# middlePCB_rev3.net
KiCad netlist of a schematic drawn in Altium Designer
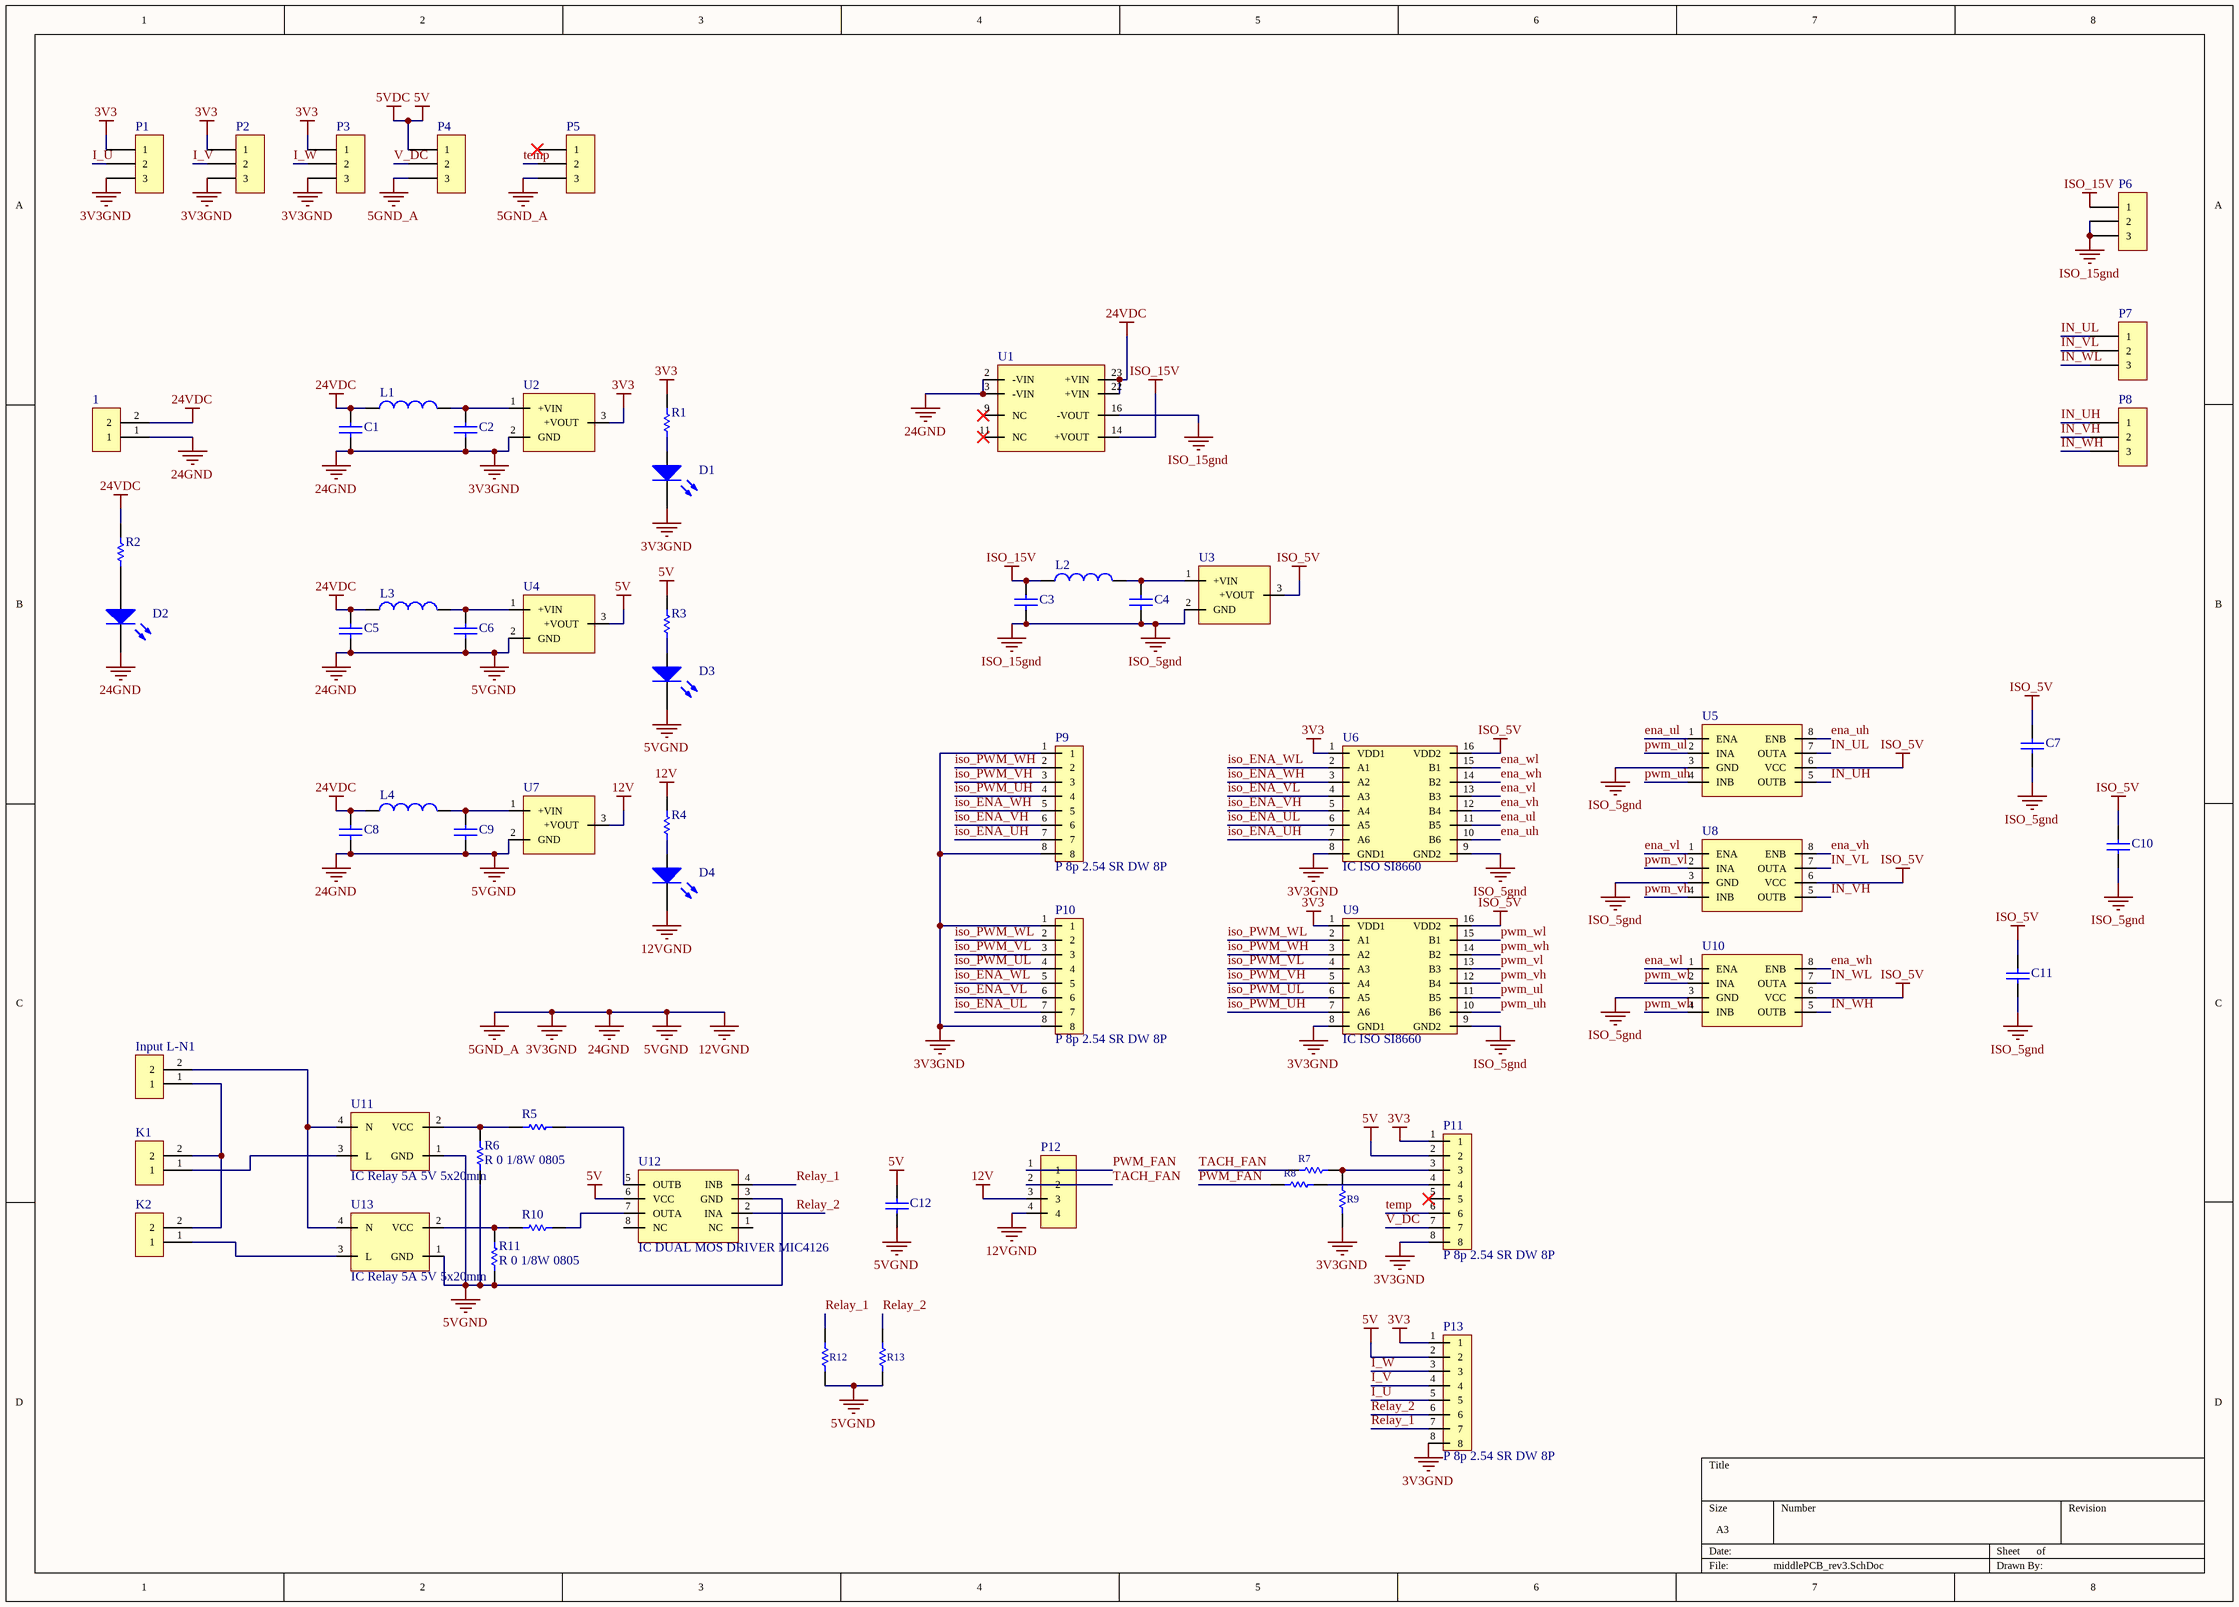
[diagram p0: middlePCB_rev3.SchDoc]

(export (version "E")
  (design (tool "Eeschema 10.0.6"))
  (components
    (comp (ref "1")
      (value "P 2p 5mm")
      (footprint "connector1x2_parafuso")
      (description "Bloques de terminales de PCB de perfil estándar RS de 5,0 mm")
      (libsource (lib "vmorais_libraries") (part "gen_purpose_conn_1x2"))
    )
    (comp (ref "C1")
      (value "C 10uF 1206 MLCC 50V X5R")
      (footprint "CAPC_1206")
      (description "Capacitores de cerâmica multicamada MLCC - SMD/SMT 1206 50V 10uF 20% X5R")
      (libsource (lib "vmorais_libraries") (part "Capacitor SMD"))
    )
    (comp (ref "C2")
      (value "C 10uF 1206 MLCC 50V X5R")
      (footprint "CAPC_1206")
      (description "Capacitores de cerâmica multicamada MLCC - SMD/SMT 1206 50V 10uF 20% X5R")
      (libsource (lib "vmorais_libraries") (part "Capacitor SMD"))
    )
    (comp (ref "C3")
      (value "C 10uF 1206 MLCC 50V X5R")
      (footprint "CAPC_1206")
      (description "Capacitores de cerâmica multicamada MLCC - SMD/SMT 1206 50V 10uF 20% X5R")
      (libsource (lib "vmorais_libraries") (part "Capacitor SMD"))
    )
    (comp (ref "C4")
      (value "C 10uF 1206 MLCC 50V X5R")
      (footprint "CAPC_1206")
      (description "Capacitores de cerâmica multicamada MLCC - SMD/SMT 1206 50V 10uF 20% X5R")
      (libsource (lib "vmorais_libraries") (part "Capacitor SMD"))
    )
    (comp (ref "C5")
      (value "C 10uF 1206 MLCC 50V X5R")
      (footprint "CAPC_1206")
      (description "Capacitores de cerâmica multicamada MLCC - SMD/SMT 1206 50V 10uF 20% X5R")
      (libsource (lib "vmorais_libraries") (part "Capacitor SMD"))
    )
    (comp (ref "C6")
      (value "C 10uF 1206 MLCC 50V X5R")
      (footprint "CAPC_1206")
      (description "Capacitores de cerâmica multicamada MLCC - SMD/SMT 1206 50V 10uF 20% X5R")
      (libsource (lib "vmorais_libraries") (part "Capacitor SMD"))
    )
    (comp (ref "C7")
      (value "C 10uF 1206 MLCC 50V X5R")
      (footprint "CAPC_1206")
      (description "Capacitores de cerâmica multicamada MLCC - SMD/SMT 1206 50V 10uF 20% X5R")
      (libsource (lib "vmorais_libraries") (part "Capacitor SMD"))
    )
    (comp (ref "C8")
      (value "C 10uF 1206 MLCC 50V X5R")
      (footprint "CAPC_1206")
      (description "Capacitores de cerâmica multicamada MLCC - SMD/SMT 1206 50V 10uF 20% X5R")
      (libsource (lib "vmorais_libraries") (part "Capacitor SMD"))
    )
    (comp (ref "C9")
      (value "C 10uF 1206 MLCC 50V X5R")
      (footprint "CAPC_1206")
      (description "Capacitores de cerâmica multicamada MLCC - SMD/SMT 1206 50V 10uF 20% X5R")
      (libsource (lib "vmorais_libraries") (part "Capacitor SMD"))
    )
    (comp (ref "C10")
      (value "C 10uF 1206 MLCC 50V X5R")
      (footprint "CAPC_1206")
      (description "Capacitores de cerâmica multicamada MLCC - SMD/SMT 1206 50V 10uF 20% X5R")
      (libsource (lib "vmorais_libraries") (part "Capacitor SMD"))
    )
    (comp (ref "C11")
      (value "C 10uF 1206 MLCC 50V X5R")
      (footprint "CAPC_1206")
      (description "Capacitores de cerâmica multicamada MLCC - SMD/SMT 1206 50V 10uF 20% X5R")
      (libsource (lib "vmorais_libraries") (part "Capacitor SMD"))
    )
    (comp (ref "C12")
      (value "C 10uF 1206 MLCC 50V X5R")
      (footprint "CAPC_1206")
      (description "Capacitores de cerâmica multicamada MLCC - SMD/SMT 1206 50V 10uF 20% X5R")
      (libsource (lib "vmorais_libraries") (part "Capacitor SMD"))
    )
    (comp (ref "D1")
      (value "IC LED 1206")
      (footprint "DIODE_1206")
      (description "LEDs padrão - SMD GREEN WATER CLEAR")
      (libsource (lib "vmorais_libraries") (part "LED"))
    )
    (comp (ref "D2")
      (value "IC LED 1206")
      (footprint "DIODE_1206")
      (description "LEDs padrão - SMD GREEN WATER CLEAR")
      (libsource (lib "vmorais_libraries") (part "LED"))
    )
    (comp (ref "D3")
      (value "IC LED 1206")
      (footprint "DIODE_1206")
      (description "LEDs padrão - SMD GREEN WATER CLEAR")
      (libsource (lib "vmorais_libraries") (part "LED"))
    )
    (comp (ref "D4")
      (value "IC LED 1206")
      (footprint "DIODE_1206")
      (description "LEDs padrão - SMD GREEN WATER CLEAR")
      (libsource (lib "vmorais_libraries") (part "LED"))
    )
    (comp (ref "Input L-N1")
      (value "P 2p 5mm")
      (footprint "connector1x2_parafuso")
      (description "Bloques de terminales de PCB de perfil estándar RS de 5,0 mm")
      (libsource (lib "vmorais_libraries") (part "gen_purpose_conn_1x2"))
    )
    (comp (ref "K1")
      (value "P 2p 5mm")
      (footprint "connector1x2_parafuso")
      (description "Bloques de terminales de PCB de perfil estándar RS de 5,0 mm")
      (libsource (lib "vmorais_libraries") (part "gen_purpose_conn_1x2"))
    )
    (comp (ref "K2")
      (value "P 2p 5mm")
      (footprint "connector1x2_parafuso")
      (description "Bloques de terminales de PCB de perfil estándar RS de 5,0 mm")
      (libsource (lib "vmorais_libraries") (part "gen_purpose_conn_1x2"))
    )
    (comp (ref "L1")
      (value "IND RLS-126")
      (footprint "Inductor - RLS-126")
      (description "Indutores fixos Line Inductors for RECOM Power Supply")
      (libsource (lib "vmorais_libraries") (part "Inductor"))
    )
    (comp (ref "L2")
      (value "IND RLS-126")
      (footprint "Inductor - RLS-126")
      (description "Indutores fixos Line Inductors for RECOM Power Supply")
      (libsource (lib "vmorais_libraries") (part "Inductor"))
    )
    (comp (ref "L3")
      (value "IND RLS-126")
      (footprint "Inductor - RLS-126")
      (description "Indutores fixos Line Inductors for RECOM Power Supply")
      (libsource (lib "vmorais_libraries") (part "Inductor"))
    )
    (comp (ref "L4")
      (value "IND RLS-126")
      (footprint "Inductor - RLS-126")
      (description "Indutores fixos Line Inductors for RECOM Power Supply")
      (libsource (lib "vmorais_libraries") (part "Inductor"))
    )
    (comp (ref "P1")
      (value "P 8p 2.54 SR DW 3P")
      (footprint "MOLEX_3p_105431_1103")
      (description "Distribuidores e Alojamento de Fios CGrid Hrd SRDW THo le 8ckt")
      (libsource (lib "vmorais_libraries") (part "Header 3"))
    )
    (comp (ref "P2")
      (value "P 8p 2.54 SR DW 3P")
      (footprint "MOLEX_3p_105431_1103")
      (description "Distribuidores e Alojamento de Fios CGrid Hrd SRDW THo le 8ckt")
      (libsource (lib "vmorais_libraries") (part "Header 3"))
    )
    (comp (ref "P3")
      (value "P 8p 2.54 SR DW 3P")
      (footprint "MOLEX_3p_105431_1103")
      (description "Distribuidores e Alojamento de Fios CGrid Hrd SRDW THo le 8ckt")
      (libsource (lib "vmorais_libraries") (part "Header 3"))
    )
    (comp (ref "P4")
      (value "P 8p 2.54 SR DW 3P")
      (footprint "MOLEX_3p_105431_1103")
      (description "Distribuidores e Alojamento de Fios CGrid Hrd SRDW THo le 8ckt")
      (libsource (lib "vmorais_libraries") (part "Header 3"))
    )
    (comp (ref "P5")
      (value "P 8p 2.54 SR DW 3P")
      (footprint "MOLEX_3p_105431_1103")
      (description "Distribuidores e Alojamento de Fios CGrid Hrd SRDW THo le 8ckt")
      (libsource (lib "vmorais_libraries") (part "Header 3"))
    )
    (comp (ref "P6")
      (value "P 8p 2.54 SR DW 3P")
      (footprint "MOLEX_3p_105431_1103")
      (description "Distribuidores e Alojamento de Fios CGrid Hrd SRDW THo le 8ckt")
      (libsource (lib "vmorais_libraries") (part "Header 3"))
    )
    (comp (ref "P7")
      (value "P 8p 2.54 SR DW 3P")
      (footprint "MOLEX_3p_105431_1103")
      (description "Distribuidores e Alojamento de Fios CGrid Hrd SRDW THo le 8ckt")
      (libsource (lib "vmorais_libraries") (part "Header 3"))
    )
    (comp (ref "P8")
      (value "P 8p 2.54 SR DW 3P")
      (footprint "MOLEX_3p_105431_1103")
      (description "Distribuidores e Alojamento de Fios CGrid Hrd SRDW THo le 8ckt")
      (libsource (lib "vmorais_libraries") (part "Header 3"))
    )
    (comp (ref "P9")
      (value "P 8p 2.54 SR DW 8P")
      (footprint "Header 8x1 8.5mm")
      (description "Distribuidores e Alojamento de Fios CGrid Hrd SRDW THo le 8ckt")
      (libsource (lib "vmorais_libraries") (part "jumper_8p"))
    )
    (comp (ref "P10")
      (value "P 8p 2.54 SR DW 8P")
      (footprint "Header 8x1 8.5mm")
      (description "Distribuidores e Alojamento de Fios CGrid Hrd SRDW THo le 8ckt")
      (libsource (lib "vmorais_libraries") (part "jumper_8p"))
    )
    (comp (ref "P11")
      (value "P 8p 2.54 SR DW 8P")
      (footprint "Header 8x1 8.5mm")
      (description "Distribuidores e Alojamento de Fios CGrid Hrd SRDW THo le 8ckt")
      (libsource (lib "vmorais_libraries") (part "jumper_8p"))
    )
    (comp (ref "P12")
      (value "P 4p 2.54 MOL FAN")
      (footprint "HEADER 4p molex")
      (description "Distribuidores e Alojamento de Fios 4 PIN HEADER WITH FR R WITH FRICTION LOCK")
      (libsource (lib "vmorais_libraries") (part "Header 4p molex"))
    )
    (comp (ref "P13")
      (value "P 8p 2.54 SR DW 8P")
      (footprint "Header 8x1 8.5mm")
      (description "Distribuidores e Alojamento de Fios CGrid Hrd SRDW THo le 8ckt")
      (libsource (lib "vmorais_libraries") (part "jumper_8p"))
    )
    (comp (ref "R1")
      (value "R 150 1/8W 0805 1%")
      (footprint "RESC_0805")
      (description "Resistores de Filme Espesso - SMD 1/8watt 150ohms 1% 100ppm")
      (libsource (lib "vmorais_libraries") (part "Resistor"))
    )
    (comp (ref "R2")
      (value "R 2k7 1/8 0805 1%")
      (footprint "RESC_0805")
      (description "Resistores de Filme Espesso - SMD 1/8watt 2.7Kohms 1% 100ppm")
      (libsource (lib "vmorais_libraries") (part "Resistor"))
    )
    (comp (ref "R3")
      (value "R 330 1/8 0805 1%")
      (footprint "RESC_0805")
      (description "Resistores de Filme Espesso - SMD 1/8Watt 330ohms 1% Commercial Use")
      (libsource (lib "vmorais_libraries") (part "Resistor"))
    )
    (comp (ref "R4")
      (value "R 1k2 1/8 0805 1%")
      (footprint "RESC_0805")
      (description "Resistores de Filme Espesso - SMD 1/8watt 1.2Kohms 1%")
      (libsource (lib "vmorais_libraries") (part "Resistor"))
    )
    (comp (ref "R5")
      (value "R 10 1/8W 0805 1%")
      (footprint "RESC_0805")
      (description "Resistores de Filme Espesso - SMD 1/8Watt 10ohms 1% Commercial Use")
      (libsource (lib "vmorais_libraries") (part "Resistor"))
    )
    (comp (ref "R6")
      (value "R 0 1/8W 0805")
      (footprint "RESC_0805")
      (description "Resistores de Filme Espesso - SMD 1/8Watt 0ohms Commercial Use")
      (libsource (lib "vmorais_libraries") (part "Resistor"))
    )
    (comp (ref "R7")
      (value "R 0 1/8W 0805")
      (footprint "RESC_0805")
      (description "Resistores de Filme Espesso - SMD 1/8Watt 0ohms Commercial Use")
      (libsource (lib "inversor_50a") (part "Resistor"))
    )
    (comp (ref "R8")
      (value "R 0 1/8W 0805")
      (footprint "RESC_0805")
      (description "Resistores de Filme Espesso - SMD 1/8Watt 0ohms Commercial Use")
      (libsource (lib "inversor_50a") (part "Resistor"))
    )
    (comp (ref "R9")
      (value "R 0 1/8W 0805")
      (footprint "RESC_0805")
      (description "Resistores de Filme Espesso - SMD 1/8Watt 0ohms Commercial Use")
      (libsource (lib "inversor_50a") (part "Resistor"))
    )
    (comp (ref "R10")
      (value "R 10 1/8W 0805 1%")
      (footprint "RESC_0805")
      (description "Resistores de Filme Espesso - SMD 1/8Watt 10ohms 1% Commercial Use")
      (libsource (lib "vmorais_libraries") (part "Resistor"))
    )
    (comp (ref "R11")
      (value "R 0 1/8W 0805")
      (footprint "RESC_0805")
      (description "Resistores de Filme Espesso - SMD 1/8Watt 0ohms Commercial Use")
      (libsource (lib "vmorais_libraries") (part "Resistor"))
    )
    (comp (ref "R12")
      (value "R 0 1/8W 0805")
      (footprint "RESC_0805")
      (description "Resistores de Filme Espesso - SMD 1/8Watt 0ohms Commercial Use")
      (libsource (lib "inversor_50a") (part "Resistor"))
    )
    (comp (ref "R13")
      (value "R 0 1/8W 0805")
      (footprint "RESC_0805")
      (description "Resistores de Filme Espesso - SMD 1/8Watt 0ohms Commercial Use")
      (libsource (lib "inversor_50a") (part "Resistor"))
    )
    (comp (ref "U1")
      (value "IC DC/DC 15V ISO")
      (footprint "MeanWell SCWNo6")
      (description "Conversores CC/CC com isolação 6W 18-36Vin 15Vout 400mA DIP24 Iso")
      (libsource (lib "vmorais_libraries") (part "MEANWELL - SCWN06"))
    )
    (comp (ref "U2")
      (value "IC DC/DC 3V3")
      (footprint "DC/DC - R-78E3.3")
      (description "Conversores CC/CC sem isolação 3.3V 500MA OUT THRU")
      (libsource (lib "vmorais_libraries") (part "DC/DC - R-78E3.3"))
    )
    (comp (ref "U3")
      (value "IC DC/DC 5V")
      (footprint "DC/DC - OKI-78SR-E")
      (description "Conversores CC/CC sem isolação 7-36Vin 5Vout 1.5A VSIP Encapsulated")
      (libsource (lib "vmorais_libraries") (part "DC/DC - R-78E3.3"))
    )
    (comp (ref "U4")
      (value "IC DC/DC 5V")
      (footprint "DC/DC - OKI-78SR-E")
      (description "Conversores CC/CC sem isolação 7-36Vin 5Vout 1.5A VSIP Encapsulated")
      (libsource (lib "vmorais_libraries") (part "DC/DC - R-78E3.3"))
    )
    (comp (ref "U5")
      (value "IC Driver 5A Dual ENA IX4340")
      (footprint "SOIC-MIC4126")
      (description "Drivers de portas Dual 5A Gate Driver IC")
      (libsource (lib "vmorais_libraries") (part "Driver - IX4340"))
    )
    (comp (ref "U6")
      (value "IC ISO SI8660")
      (footprint "SOIC127P610X155-16N")
      (description "Isoladores digitais 1 kV 6-channel digital isolator")
      (libsource (lib "vmorais_libraries") (part "ISO SI8660"))
    )
    (comp (ref "U7")
      (value "IC DC/DC 12V")
      (footprint "DC/DC - OKI-78SR-E")
      (description "Conversores CC/CC sem isolação 15-36Vin 12Vout 1.0A VSIP Encapsulated")
      (libsource (lib "vmorais_libraries") (part "DC/DC - R-78E3.3"))
    )
    (comp (ref "U8")
      (value "IC Driver 5A Dual ENA IX4340")
      (footprint "SOIC-MIC4126")
      (description "Drivers de portas Dual 5A Gate Driver IC")
      (libsource (lib "vmorais_libraries") (part "Driver - IX4340"))
    )
    (comp (ref "U9")
      (value "IC ISO SI8660")
      (footprint "SOIC127P610X155-16N")
      (description "Isoladores digitais 1 kV 6-channel digital isolator")
      (libsource (lib "vmorais_libraries") (part "ISO SI8660"))
    )
    (comp (ref "U10")
      (value "IC Driver 5A Dual ENA IX4340")
      (footprint "SOIC-MIC4126")
      (description "Drivers de portas Dual 5A Gate Driver IC")
      (libsource (lib "vmorais_libraries") (part "Driver - IX4340"))
    )
    (comp (ref "U11")
      (value "IC Relay 5A 5V 5x20mm")
      (footprint "Relay - G6DN")
      (description "Relés para uso geral 1 form A w/ 5VDC Coil-standard type")
      (libsource (lib "vmorais_libraries") (part "Relay - G6DN"))
    )
    (comp (ref "U12")
      (value "IC DUAL MOS DRIVER MIC4126")
      (footprint "SOIC-MIC4126")
      (description "Drivers de portas 1.5A Dual High Speed MOSFET Driver with Low Thermal Impedance")
      (libsource (lib "vmorais_libraries") (part "MOS_DRIVER-MIC4126"))
    )
    (comp (ref "U13")
      (value "IC Relay 5A 5V 5x20mm")
      (footprint "Relay - G6DN")
      (description "Relés para uso geral 1 form A w/ 5VDC Coil-standard type")
      (libsource (lib "vmorais_libraries") (part "Relay - G6DN"))
    )
  )
  (nets
    (net (code "1") (name "/IN_UH") (class "Default")
      (node (ref "P8") (pin "1") (pinfunction "1_1") (pintype "passive"))
      (node (ref "U5") (pin "5") (pinfunction "OUTB_5") (pintype "passive"))
    )
    (net (code "2") (name "/IN_UL") (class "Default")
      (node (ref "P7") (pin "1") (pinfunction "1_1") (pintype "passive"))
      (node (ref "U5") (pin "7") (pinfunction "OUTA_7") (pintype "passive"))
    )
    (net (code "3") (name "/IN_VH") (class "Default")
      (node (ref "P8") (pin "2") (pinfunction "2_2") (pintype "passive"))
      (node (ref "U8") (pin "5") (pinfunction "OUTB_5") (pintype "passive"))
    )
    (net (code "4") (name "/IN_VL") (class "Default")
      (node (ref "P7") (pin "2") (pinfunction "2_2") (pintype "passive"))
      (node (ref "U8") (pin "7") (pinfunction "OUTA_7") (pintype "passive"))
    )
    (net (code "5") (name "/IN_WH") (class "Default")
      (node (ref "P8") (pin "3") (pinfunction "3_3") (pintype "passive"))
      (node (ref "U10") (pin "5") (pinfunction "OUTB_5") (pintype "passive"))
    )
    (net (code "6") (name "/IN_WL") (class "Default")
      (node (ref "P7") (pin "3") (pinfunction "3_3") (pintype "passive"))
      (node (ref "U10") (pin "7") (pinfunction "OUTA_7") (pintype "passive"))
    )
    (net (code "7") (name "/I_U") (class "Default")
      (node (ref "P1") (pin "2") (pinfunction "2_2") (pintype "passive"))
      (node (ref "P13") (pin "5") (pinfunction "5_5") (pintype "passive"))
    )
    (net (code "8") (name "/I_V") (class "Default")
      (node (ref "P13") (pin "4") (pinfunction "4_4") (pintype "passive"))
      (node (ref "P2") (pin "2") (pinfunction "2_2") (pintype "passive"))
    )
    (net (code "9") (name "/I_W") (class "Default")
      (node (ref "P13") (pin "3") (pinfunction "3_3") (pintype "passive"))
      (node (ref "P3") (pin "2") (pinfunction "2_2") (pintype "passive"))
    )
    (net (code "10") (name "/PWM_FAN") (class "Default")
      (node (ref "P12") (pin "1") (pinfunction "1_1") (pintype "passive"))
      (node (ref "R8") (pin "1") (pinfunction "1_1") (pintype "passive"))
    )
    (net (code "11") (name "/Relay_1") (class "Default")
      (node (ref "P13") (pin "7") (pinfunction "7_7") (pintype "passive"))
      (node (ref "R12") (pin "2") (pinfunction "2_2") (pintype "passive"))
      (node (ref "U12") (pin "4") (pinfunction "INB_4") (pintype "passive"))
    )
    (net (code "12") (name "/Relay_2") (class "Default")
      (node (ref "P13") (pin "6") (pinfunction "6_6") (pintype "passive"))
      (node (ref "R13") (pin "2") (pinfunction "2_2") (pintype "passive"))
      (node (ref "U12") (pin "2") (pinfunction "INA_2") (pintype "passive"))
    )
    (net (code "13") (name "/TACH_FAN") (class "Default")
      (node (ref "P12") (pin "2") (pinfunction "2_2") (pintype "passive"))
      (node (ref "R7") (pin "1") (pinfunction "1_1") (pintype "passive"))
    )
    (net (code "14") (name "/V_DC") (class "Default")
      (node (ref "P11") (pin "7") (pinfunction "7_7") (pintype "passive"))
      (node (ref "P4") (pin "2") (pinfunction "2_2") (pintype "passive"))
    )
    (net (code "15") (name "/ena_uh") (class "Default")
      (node (ref "U5") (pin "8") (pinfunction "ENB_8") (pintype "passive"))
      (node (ref "U6") (pin "10") (pinfunction "B6_10") (pintype "passive"))
    )
    (net (code "16") (name "/ena_ul") (class "Default")
      (node (ref "U5") (pin "1") (pinfunction "ENA_1") (pintype "passive"))
      (node (ref "U6") (pin "11") (pinfunction "B5_11") (pintype "passive"))
    )
    (net (code "17") (name "/ena_vh") (class "Default")
      (node (ref "U6") (pin "12") (pinfunction "B4_12") (pintype "passive"))
      (node (ref "U8") (pin "8") (pinfunction "ENB_8") (pintype "passive"))
    )
    (net (code "18") (name "/ena_vl") (class "Default")
      (node (ref "U6") (pin "13") (pinfunction "B3_13") (pintype "passive"))
      (node (ref "U8") (pin "1") (pinfunction "ENA_1") (pintype "passive"))
    )
    (net (code "19") (name "/ena_wh") (class "Default")
      (node (ref "U10") (pin "8") (pinfunction "ENB_8") (pintype "passive"))
      (node (ref "U6") (pin "14") (pinfunction "B2_14") (pintype "passive"))
    )
    (net (code "20") (name "/ena_wl") (class "Default")
      (node (ref "U10") (pin "1") (pinfunction "ENA_1") (pintype "passive"))
      (node (ref "U6") (pin "15") (pinfunction "B1_15") (pintype "passive"))
    )
    (net (code "21") (name "/iso_ENA_UH") (class "Default")
      (node (ref "P9") (pin "7") (pinfunction "7_7") (pintype "passive"))
      (node (ref "U6") (pin "7") (pinfunction "A6_7") (pintype "passive"))
    )
    (net (code "22") (name "/iso_ENA_UL") (class "Default")
      (node (ref "P10") (pin "7") (pinfunction "7_7") (pintype "passive"))
      (node (ref "U6") (pin "6") (pinfunction "A5_6") (pintype "passive"))
    )
    (net (code "23") (name "/iso_ENA_VH") (class "Default")
      (node (ref "P9") (pin "6") (pinfunction "6_6") (pintype "passive"))
      (node (ref "U6") (pin "5") (pinfunction "A4_5") (pintype "passive"))
    )
    (net (code "24") (name "/iso_ENA_VL") (class "Default")
      (node (ref "P10") (pin "6") (pinfunction "6_6") (pintype "passive"))
      (node (ref "U6") (pin "4") (pinfunction "A3_4") (pintype "passive"))
    )
    (net (code "25") (name "/iso_ENA_WH") (class "Default")
      (node (ref "P9") (pin "5") (pinfunction "5_5") (pintype "passive"))
      (node (ref "U6") (pin "3") (pinfunction "A2_3") (pintype "passive"))
    )
    (net (code "26") (name "/iso_ENA_WL") (class "Default")
      (node (ref "P10") (pin "5") (pinfunction "5_5") (pintype "passive"))
      (node (ref "U6") (pin "2") (pinfunction "A1_2") (pintype "passive"))
    )
    (net (code "27") (name "/iso_PWM_UH") (class "Default")
      (node (ref "P9") (pin "4") (pinfunction "4_4") (pintype "passive"))
      (node (ref "U9") (pin "7") (pinfunction "A6_7") (pintype "passive"))
    )
    (net (code "28") (name "/iso_PWM_UL") (class "Default")
      (node (ref "P10") (pin "4") (pinfunction "4_4") (pintype "passive"))
      (node (ref "U9") (pin "6") (pinfunction "A5_6") (pintype "passive"))
    )
    (net (code "29") (name "/iso_PWM_VH") (class "Default")
      (node (ref "P9") (pin "3") (pinfunction "3_3") (pintype "passive"))
      (node (ref "U9") (pin "5") (pinfunction "A4_5") (pintype "passive"))
    )
    (net (code "30") (name "/iso_PWM_VL") (class "Default")
      (node (ref "P10") (pin "3") (pinfunction "3_3") (pintype "passive"))
      (node (ref "U9") (pin "4") (pinfunction "A3_4") (pintype "passive"))
    )
    (net (code "31") (name "/iso_PWM_WH") (class "Default")
      (node (ref "P9") (pin "2") (pinfunction "2_2") (pintype "passive"))
      (node (ref "U9") (pin "3") (pinfunction "A2_3") (pintype "passive"))
    )
    (net (code "32") (name "/iso_PWM_WL") (class "Default")
      (node (ref "P10") (pin "2") (pinfunction "2_2") (pintype "passive"))
      (node (ref "U9") (pin "2") (pinfunction "A1_2") (pintype "passive"))
    )
    (net (code "33") (name "/pwm_uh") (class "Default")
      (node (ref "U5") (pin "4") (pinfunction "INB_4") (pintype "passive"))
      (node (ref "U9") (pin "10") (pinfunction "B6_10") (pintype "passive"))
    )
    (net (code "34") (name "/pwm_ul") (class "Default")
      (node (ref "U5") (pin "2") (pinfunction "INA_2") (pintype "passive"))
      (node (ref "U9") (pin "11") (pinfunction "B5_11") (pintype "passive"))
    )
    (net (code "35") (name "/pwm_vh") (class "Default")
      (node (ref "U8") (pin "4") (pinfunction "INB_4") (pintype "passive"))
      (node (ref "U9") (pin "12") (pinfunction "B4_12") (pintype "passive"))
    )
    (net (code "36") (name "/pwm_vl") (class "Default")
      (node (ref "U8") (pin "2") (pinfunction "INA_2") (pintype "passive"))
      (node (ref "U9") (pin "13") (pinfunction "B3_13") (pintype "passive"))
    )
    (net (code "37") (name "/pwm_wh") (class "Default")
      (node (ref "U10") (pin "4") (pinfunction "INB_4") (pintype "passive"))
      (node (ref "U9") (pin "14") (pinfunction "B2_14") (pintype "passive"))
    )
    (net (code "38") (name "/pwm_wl") (class "Default")
      (node (ref "U10") (pin "2") (pinfunction "INA_2") (pintype "passive"))
      (node (ref "U9") (pin "15") (pinfunction "B1_15") (pintype "passive"))
    )
    (net (code "39") (name "/temp") (class "Default")
      (node (ref "P11") (pin "6") (pinfunction "6_6") (pintype "passive"))
      (node (ref "P5") (pin "2") (pinfunction "2_2") (pintype "passive"))
    )
    (net (code "40") (name "3V3") (class "Default")
      (node (ref "P1") (pin "1") (pinfunction "1_1") (pintype "passive"))
      (node (ref "P11") (pin "1") (pinfunction "1_1") (pintype "passive"))
      (node (ref "P13") (pin "1") (pinfunction "1_1") (pintype "passive"))
      (node (ref "P2") (pin "1") (pinfunction "1_1") (pintype "passive"))
      (node (ref "P3") (pin "1") (pinfunction "1_1") (pintype "passive"))
      (node (ref "R1") (pin "2") (pinfunction "2_2") (pintype "passive"))
      (node (ref "U2") (pin "3") (pinfunction "+VOUT_3") (pintype "passive"))
      (node (ref "U6") (pin "1") (pinfunction "VDD1_1") (pintype "passive"))
      (node (ref "U9") (pin "1") (pinfunction "VDD1_1") (pintype "passive"))
    )
    (net (code "41") (name "5V") (class "Default")
      (node (ref "C12") (pin "2") (pinfunction "2_2") (pintype "passive"))
      (node (ref "P11") (pin "2") (pinfunction "2_2") (pintype "passive"))
      (node (ref "P13") (pin "2") (pinfunction "2_2") (pintype "passive"))
      (node (ref "P4") (pin "1") (pinfunction "1_1") (pintype "passive"))
      (node (ref "R3") (pin "2") (pinfunction "2_2") (pintype "passive"))
      (node (ref "U12") (pin "6") (pinfunction "VCC_6") (pintype "passive"))
      (node (ref "U4") (pin "3") (pinfunction "+VOUT_3") (pintype "passive"))
    )
    (net (code "42") (name "12V") (class "Default")
      (node (ref "P12") (pin "3") (pinfunction "3_3") (pintype "passive"))
      (node (ref "R4") (pin "2") (pinfunction "2_2") (pintype "passive"))
      (node (ref "U7") (pin "3") (pinfunction "+VOUT_3") (pintype "passive"))
    )
    (net (code "43") (name "12VGND") (class "Default")
      (node (ref "1") (pin "1") (pinfunction "1_1") (pintype "passive"))
      (node (ref "C1") (pin "1") (pinfunction "1_1") (pintype "passive"))
      (node (ref "C12") (pin "1") (pinfunction "1_1") (pintype "passive"))
      (node (ref "C2") (pin "1") (pinfunction "1_1") (pintype "passive"))
      (node (ref "C5") (pin "1") (pinfunction "1_1") (pintype "passive"))
      (node (ref "C6") (pin "1") (pinfunction "1_1") (pintype "passive"))
      (node (ref "C8") (pin "1") (pinfunction "1_1") (pintype "passive"))
      (node (ref "C9") (pin "1") (pinfunction "1_1") (pintype "passive"))
      (node (ref "D1") (pin "2") (pinfunction "K_2") (pintype "passive"))
      (node (ref "D2") (pin "2") (pinfunction "K_2") (pintype "passive"))
      (node (ref "D3") (pin "2") (pinfunction "K_2") (pintype "passive"))
      (node (ref "D4") (pin "2") (pinfunction "K_2") (pintype "passive"))
      (node (ref "P1") (pin "3") (pinfunction "3_3") (pintype "passive"))
      (node (ref "P10") (pin "1") (pinfunction "1_1") (pintype "passive"))
      (node (ref "P10") (pin "8") (pinfunction "8_8") (pintype "passive"))
      (node (ref "P11") (pin "8") (pinfunction "8_8") (pintype "passive"))
      (node (ref "P12") (pin "4") (pinfunction "4_4") (pintype "passive"))
      (node (ref "P13") (pin "8") (pinfunction "8_8") (pintype "passive"))
      (node (ref "P2") (pin "3") (pinfunction "3_3") (pintype "passive"))
      (node (ref "P3") (pin "3") (pinfunction "3_3") (pintype "passive"))
      (node (ref "P4") (pin "3") (pinfunction "3_3") (pintype "passive"))
      (node (ref "P5") (pin "3") (pinfunction "3_3") (pintype "passive"))
      (node (ref "P9") (pin "1") (pinfunction "1_1") (pintype "passive"))
      (node (ref "P9") (pin "8") (pinfunction "8_8") (pintype "passive"))
      (node (ref "R11") (pin "2") (pinfunction "2_2") (pintype "passive"))
      (node (ref "R12") (pin "1") (pinfunction "1_1") (pintype "passive"))
      (node (ref "R13") (pin "1") (pinfunction "1_1") (pintype "passive"))
      (node (ref "R6") (pin "2") (pinfunction "2_2") (pintype "passive"))
      (node (ref "R9") (pin "1") (pinfunction "1_1") (pintype "passive"))
      (node (ref "U1") (pin "2") (pinfunction "-VIN_2") (pintype "passive"))
      (node (ref "U1") (pin "3") (pinfunction "-VIN_3") (pintype "passive"))
      (node (ref "U11") (pin "1") (pinfunction "GND_1") (pintype "passive"))
      (node (ref "U12") (pin "3") (pinfunction "GND_3") (pintype "passive"))
      (node (ref "U13") (pin "1") (pinfunction "GND_1") (pintype "passive"))
      (node (ref "U2") (pin "2") (pinfunction "GND_2") (pintype "passive"))
      (node (ref "U4") (pin "2") (pinfunction "GND_2") (pintype "passive"))
      (node (ref "U6") (pin "8") (pinfunction "GND1_8") (pintype "passive"))
      (node (ref "U7") (pin "2") (pinfunction "GND_2") (pintype "passive"))
      (node (ref "U9") (pin "8") (pinfunction "GND1_8") (pintype "passive"))
    )
    (net (code "44") (name "24VDC") (class "Default")
      (node (ref "1") (pin "2") (pinfunction "2_2") (pintype "passive"))
      (node (ref "C1") (pin "2") (pinfunction "2_2") (pintype "passive"))
      (node (ref "C5") (pin "2") (pinfunction "2_2") (pintype "passive"))
      (node (ref "C8") (pin "2") (pinfunction "2_2") (pintype "passive"))
      (node (ref "L1") (pin "1") (pinfunction "1_1") (pintype "passive"))
      (node (ref "L3") (pin "1") (pinfunction "1_1") (pintype "passive"))
      (node (ref "L4") (pin "1") (pinfunction "1_1") (pintype "passive"))
      (node (ref "R2") (pin "2") (pinfunction "2_2") (pintype "passive"))
      (node (ref "U1") (pin "22") (pinfunction "+VIN_22") (pintype "passive"))
      (node (ref "U1") (pin "23") (pinfunction "+VIN_23") (pintype "passive"))
    )
    (net (code "45") (name "ISO_5V") (class "Default")
      (node (ref "C10") (pin "2") (pinfunction "2_2") (pintype "passive"))
      (node (ref "C11") (pin "2") (pinfunction "2_2") (pintype "passive"))
      (node (ref "C7") (pin "2") (pinfunction "2_2") (pintype "passive"))
      (node (ref "U10") (pin "6") (pinfunction "VCC_6") (pintype "passive"))
      (node (ref "U3") (pin "3") (pinfunction "+VOUT_3") (pintype "passive"))
      (node (ref "U5") (pin "6") (pinfunction "VCC_6") (pintype "passive"))
      (node (ref "U6") (pin "16") (pinfunction "VDD2_16") (pintype "passive"))
      (node (ref "U8") (pin "6") (pinfunction "VCC_6") (pintype "passive"))
      (node (ref "U9") (pin "16") (pinfunction "VDD2_16") (pintype "passive"))
    )
    (net (code "46") (name "ISO_15V") (class "Default")
      (node (ref "C3") (pin "2") (pinfunction "2_2") (pintype "passive"))
      (node (ref "L2") (pin "1") (pinfunction "1_1") (pintype "passive"))
      (node (ref "P6") (pin "1") (pinfunction "1_1") (pintype "passive"))
      (node (ref "U1") (pin "14") (pinfunction "+VOUT_14") (pintype "passive"))
    )
    (net (code "47") (name "ISO_15gnd") (class "Default")
      (node (ref "C10") (pin "1") (pinfunction "1_1") (pintype "passive"))
      (node (ref "C11") (pin "1") (pinfunction "1_1") (pintype "passive"))
      (node (ref "C3") (pin "1") (pinfunction "1_1") (pintype "passive"))
      (node (ref "C4") (pin "1") (pinfunction "1_1") (pintype "passive"))
      (node (ref "C7") (pin "1") (pinfunction "1_1") (pintype "passive"))
      (node (ref "P6") (pin "2") (pinfunction "2_2") (pintype "passive"))
      (node (ref "P6") (pin "3") (pinfunction "3_3") (pintype "passive"))
      (node (ref "U1") (pin "16") (pinfunction "-VOUT_16") (pintype "passive"))
      (node (ref "U10") (pin "3") (pinfunction "GND_3") (pintype "passive"))
      (node (ref "U3") (pin "2") (pinfunction "GND_2") (pintype "passive"))
      (node (ref "U5") (pin "3") (pinfunction "GND_3") (pintype "passive"))
      (node (ref "U6") (pin "9") (pinfunction "GND2_9") (pintype "passive"))
      (node (ref "U8") (pin "3") (pinfunction "GND_3") (pintype "passive"))
      (node (ref "U9") (pin "9") (pinfunction "GND2_9") (pintype "passive"))
    )
    (net (code "48") (name "Net-(D1-A)") (class "Default")
      (node (ref "D1") (pin "1") (pinfunction "A_1") (pintype "passive"))
      (node (ref "R1") (pin "1") (pinfunction "1_1") (pintype "passive"))
    )
    (net (code "49") (name "Net-(D2-A)") (class "Default")
      (node (ref "D2") (pin "1") (pinfunction "A_1") (pintype "passive"))
      (node (ref "R2") (pin "1") (pinfunction "1_1") (pintype "passive"))
    )
    (net (code "50") (name "Net-(D3-A)") (class "Default")
      (node (ref "D3") (pin "1") (pinfunction "A_1") (pintype "passive"))
      (node (ref "R3") (pin "1") (pinfunction "1_1") (pintype "passive"))
    )
    (net (code "51") (name "Net-(D4-A)") (class "Default")
      (node (ref "D4") (pin "1") (pinfunction "A_1") (pintype "passive"))
      (node (ref "R4") (pin "1") (pinfunction "1_1") (pintype "passive"))
    )
    (net (code "52") (name "Net-(Input L-N1-Pad1)") (class "Default")
      (node (ref "Input L-N1") (pin "1") (pinfunction "1_1") (pintype "passive"))
      (node (ref "K1") (pin "2") (pinfunction "2_2") (pintype "passive"))
      (node (ref "K2") (pin "2") (pinfunction "2_2") (pintype "passive"))
    )
    (net (code "53") (name "Net-(P11-Pad3)") (class "Default")
      (node (ref "P11") (pin "3") (pinfunction "3_3") (pintype "passive"))
      (node (ref "R7") (pin "2") (pinfunction "2_2") (pintype "passive"))
      (node (ref "R9") (pin "2") (pinfunction "2_2") (pintype "passive"))
    )
    (net (code "54") (name "Net-(P11-Pad4)") (class "Default")
      (node (ref "P11") (pin "4") (pinfunction "4_4") (pintype "passive"))
      (node (ref "R8") (pin "2") (pinfunction "2_2") (pintype "passive"))
    )
    (net (code "55") (name "Net-(U2-+VIN)") (class "Default")
      (node (ref "C2") (pin "2") (pinfunction "2_2") (pintype "passive"))
      (node (ref "L1") (pin "2") (pinfunction "2_2") (pintype "passive"))
      (node (ref "U2") (pin "1") (pinfunction "+VIN_1") (pintype "passive"))
    )
    (net (code "56") (name "Net-(U3-+VIN)") (class "Default")
      (node (ref "C4") (pin "2") (pinfunction "2_2") (pintype "passive"))
      (node (ref "L2") (pin "2") (pinfunction "2_2") (pintype "passive"))
      (node (ref "U3") (pin "1") (pinfunction "+VIN_1") (pintype "passive"))
    )
    (net (code "57") (name "Net-(U4-+VIN)") (class "Default")
      (node (ref "C6") (pin "2") (pinfunction "2_2") (pintype "passive"))
      (node (ref "L3") (pin "2") (pinfunction "2_2") (pintype "passive"))
      (node (ref "U4") (pin "1") (pinfunction "+VIN_1") (pintype "passive"))
    )
    (net (code "58") (name "Net-(U7-+VIN)") (class "Default")
      (node (ref "C9") (pin "2") (pinfunction "2_2") (pintype "passive"))
      (node (ref "L4") (pin "2") (pinfunction "2_2") (pintype "passive"))
      (node (ref "U7") (pin "1") (pinfunction "+VIN_1") (pintype "passive"))
    )
    (net (code "59") (name "Net-(U11-L)") (class "Default")
      (node (ref "K1") (pin "1") (pinfunction "1_1") (pintype "passive"))
      (node (ref "U11") (pin "3") (pinfunction "L_3") (pintype "passive"))
    )
    (net (code "60") (name "Net-(U11-N)") (class "Default")
      (node (ref "Input L-N1") (pin "2") (pinfunction "2_2") (pintype "passive"))
      (node (ref "U11") (pin "4") (pinfunction "N_4") (pintype "passive"))
      (node (ref "U13") (pin "4") (pinfunction "N_4") (pintype "passive"))
    )
    (net (code "61") (name "Net-(U11-VCC)") (class "Default")
      (node (ref "R5") (pin "2") (pinfunction "2_2") (pintype "passive"))
      (node (ref "R6") (pin "1") (pinfunction "1_1") (pintype "passive"))
      (node (ref "U11") (pin "2") (pinfunction "VCC_2") (pintype "passive"))
    )
    (net (code "62") (name "Net-(U12-OUTA)") (class "Default")
      (node (ref "R10") (pin "1") (pinfunction "1_1") (pintype "passive"))
      (node (ref "U12") (pin "7") (pinfunction "OUTA_7") (pintype "passive"))
    )
    (net (code "63") (name "Net-(U12-OUTB)") (class "Default")
      (node (ref "R5") (pin "1") (pinfunction "1_1") (pintype "passive"))
      (node (ref "U12") (pin "5") (pinfunction "OUTB_5") (pintype "passive"))
    )
    (net (code "64") (name "Net-(U13-L)") (class "Default")
      (node (ref "K2") (pin "1") (pinfunction "1_1") (pintype "passive"))
      (node (ref "U13") (pin "3") (pinfunction "L_3") (pintype "passive"))
    )
    (net (code "65") (name "Net-(U13-VCC)") (class "Default")
      (node (ref "R10") (pin "2") (pinfunction "2_2") (pintype "passive"))
      (node (ref "R11") (pin "1") (pinfunction "1_1") (pintype "passive"))
      (node (ref "U13") (pin "2") (pinfunction "VCC_2") (pintype "passive"))
    )
    (net (code "66") (name "unconnected-(P5-Pad1)") (class "Default")
      (node (ref "P5") (pin "1") (pinfunction "1_1") (pintype "passive+no_connect"))
    )
    (net (code "67") (name "unconnected-(P11-Pad5)") (class "Default")
      (node (ref "P11") (pin "5") (pinfunction "5_5") (pintype "passive+no_connect"))
    )
    (net (code "68") (name "unconnected-(U1-NC-Pad9)") (class "Default")
      (node (ref "U1") (pin "9") (pinfunction "NC_9") (pintype "passive+no_connect"))
    )
    (net (code "69") (name "unconnected-(U1-NC-Pad11)") (class "Default")
      (node (ref "U1") (pin "11") (pinfunction "NC_11") (pintype "passive+no_connect"))
    )
    (net (code "70") (name "unconnected-(U12-NC-Pad1)") (class "Default")
      (node (ref "U12") (pin "1") (pinfunction "NC_1") (pintype "passive"))
    )
    (net (code "71") (name "unconnected-(U12-NC-Pad8)") (class "Default")
      (node (ref "U12") (pin "8") (pinfunction "NC_8") (pintype "passive"))
    )
  )
)
